# BCARDLIGHT.net
KiCad netlist of a schematic drawn in EAGLE
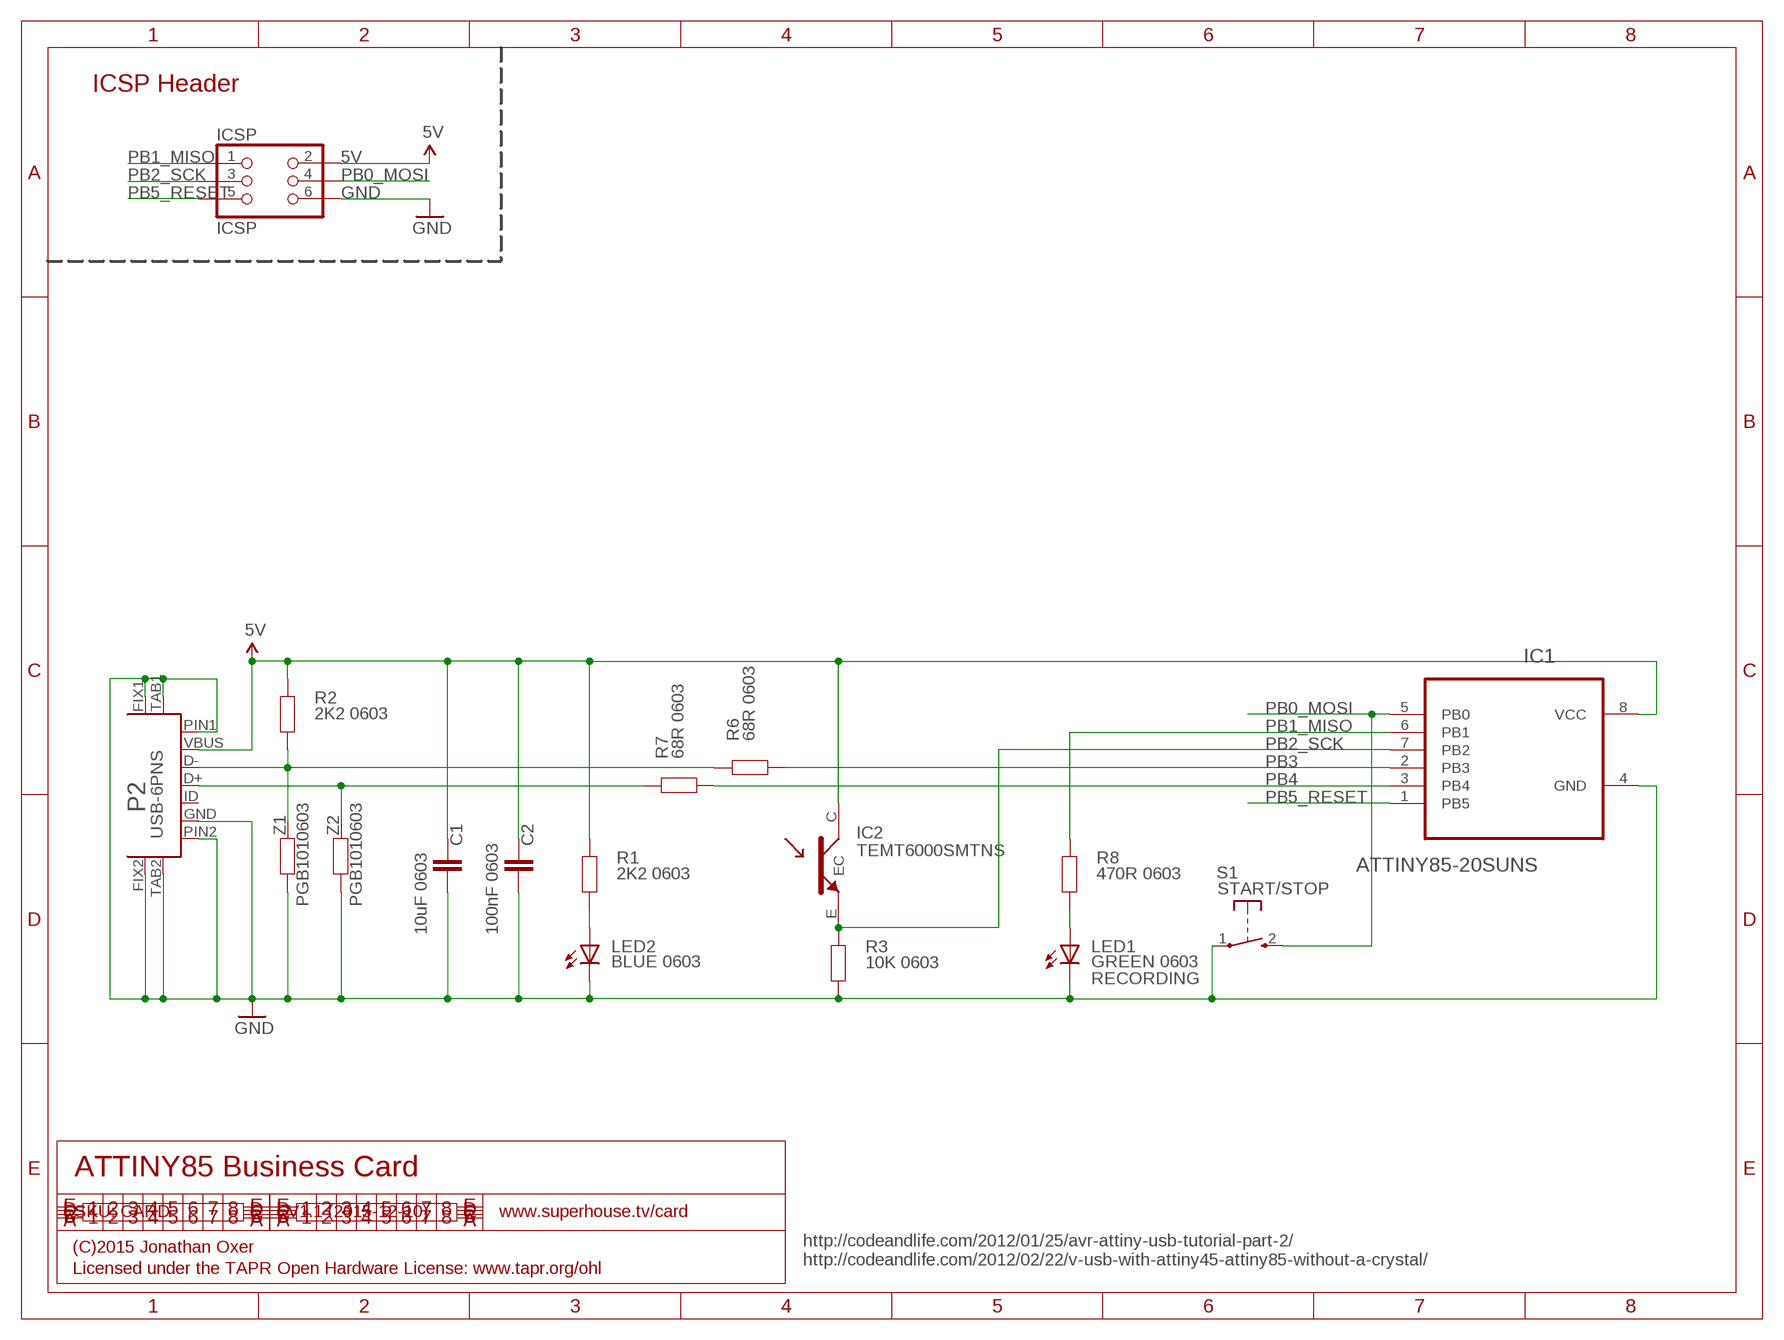
[diagram p0: schematic, sheet 1]

(export (version "E")
  (design (tool "Eeschema 10.0.6"))
  (components
    (comp (ref "C1")
      (value "10uF 0603")
      (footprint "eagle-import:0603_NO_SILK")
      (libsource (lib "eagle-import") (part "CAPNS"))
    )
    (comp (ref "C2")
      (value "100nF 0603")
      (footprint "eagle-import:0603_NO_SILK")
      (libsource (lib "eagle-import") (part "CAPNS"))
    )
    (comp (ref "IC1")
      (value "ATTINY85-20SUNS")
      (footprint "eagle-import:SOIC127P798X216-8N_NO_SILK")
      (libsource (lib "eagle-import") (part "ATTINY85-20SUNS"))
    )
    (comp (ref "IC2")
      (value "TEMT6000SMTNS")
      (footprint "eagle-import:TEMT6000_NO_SILK")
      (libsource (lib "eagle-import") (part "TEMT6000SMTNS"))
    )
    (comp (ref "ICSP")
      (value "ICSP")
      (footprint "eagle-import:2X03SURFACE_NO_SILK")
      (libsource (lib "eagle-import") (part "ICSPSMTNS"))
    )
    (comp (ref "LED1")
      (value "GREEN 0603")
      (footprint "eagle-import:0603_NO_SILK")
      (libsource (lib "eagle-import") (part "LED0603NS"))
    )
    (comp (ref "LED2")
      (value "BLUE 0603")
      (footprint "eagle-import:0603_NO_SILK")
      (libsource (lib "eagle-import") (part "LED0603NS"))
    )
    (comp (ref "P2")
      (value "USB-6PNS")
      (footprint "eagle-import:USB-MICROB-MB05PMXX_NO_SILK")
      (libsource (lib "eagle-import") (part "USB-6PNS"))
    )
    (comp (ref "R1")
      (value "2K2 0603")
      (footprint "eagle-import:0603_NO_SILK")
      (libsource (lib "eagle-import") (part "RESISTOR0603NS"))
    )
    (comp (ref "R2")
      (value "2K2 0603")
      (footprint "eagle-import:0603_NO_SILK")
      (libsource (lib "eagle-import") (part "RESISTOR0603NS"))
    )
    (comp (ref "R3")
      (value "10K 0603")
      (footprint "eagle-import:0603_NO_SILK")
      (libsource (lib "eagle-import") (part "RESISTOR0603NS"))
    )
    (comp (ref "R6")
      (value "68R 0603")
      (footprint "eagle-import:0603_NO_SILK")
      (libsource (lib "eagle-import") (part "RESISTOR0603NS"))
    )
    (comp (ref "R7")
      (value "68R 0603")
      (footprint "eagle-import:0603_NO_SILK")
      (libsource (lib "eagle-import") (part "RESISTOR0603NS"))
    )
    (comp (ref "R8")
      (value "470R 0603")
      (footprint "eagle-import:0603_NO_SILK")
      (libsource (lib "eagle-import") (part "RESISTOR0603NS"))
    )
    (comp (ref "S1")
      (value "START/STOP")
      (footprint "eagle-import:TACTILE_SWITCH_SMD_2PIN_TINY_NO_SILK")
      (libsource (lib "eagle-import") (part "TAC_SWITCH_2PINNS"))
    )
    (comp (ref "Z1")
      (value "PGB1010603")
      (footprint "eagle-import:0603_NO_SILK")
      (libsource (lib "eagle-import") (part "RESISTOR0603NS"))
    )
    (comp (ref "Z2")
      (value "PGB1010603")
      (footprint "eagle-import:0603_NO_SILK")
      (libsource (lib "eagle-import") (part "RESISTOR0603NS"))
    )
  )
  (nets
    (net (code "1") (name "/PB0_MOSI") (class "Default")
      (node (ref "IC1") (pin "5") (pinfunction "PB0_5") (pintype "bidirectional"))
      (node (ref "ICSP") (pin "4") (pinfunction "4_4") (pintype "passive"))
      (node (ref "S1") (pin "2") (pinfunction "S_2") (pintype "passive"))
    )
    (net (code "2") (name "/PB1_MISO") (class "Default")
      (node (ref "IC1") (pin "6") (pinfunction "PB1_6") (pintype "bidirectional"))
      (node (ref "ICSP") (pin "1") (pinfunction "1_1") (pintype "passive"))
      (node (ref "R8") (pin "2") (pinfunction "2_2") (pintype "passive"))
    )
    (net (code "3") (name "/PB2_SCK") (class "Default")
      (node (ref "IC1") (pin "7") (pinfunction "PB2_7") (pintype "bidirectional"))
      (node (ref "IC2") (pin "E") (pinfunction "E_E") (pintype "bidirectional"))
      (node (ref "ICSP") (pin "3") (pinfunction "3_3") (pintype "passive"))
      (node (ref "R3") (pin "2") (pinfunction "2_2") (pintype "passive"))
    )
    (net (code "4") (name "/PB3") (class "Default")
      (node (ref "IC1") (pin "2") (pinfunction "PB3_2") (pintype "bidirectional"))
      (node (ref "R6") (pin "1") (pinfunction "1_1") (pintype "passive"))
    )
    (net (code "5") (name "/PB4") (class "Default")
      (node (ref "IC1") (pin "3") (pinfunction "PB4_3") (pintype "bidirectional"))
      (node (ref "R7") (pin "1") (pinfunction "1_1") (pintype "passive"))
    )
    (net (code "6") (name "/PB5_RESET") (class "Default")
      (node (ref "IC1") (pin "1") (pinfunction "PB5_1") (pintype "bidirectional"))
      (node (ref "ICSP") (pin "5") (pinfunction "5_5") (pintype "passive"))
    )
    (net (code "7") (name "5V") (class "Default")
      (node (ref "C1") (pin "1") (pinfunction "1_1") (pintype "passive"))
      (node (ref "C2") (pin "1") (pinfunction "1_1") (pintype "passive"))
      (node (ref "IC1") (pin "8") (pinfunction "VCC_8") (pintype "power_in"))
      (node (ref "IC2") (pin "C") (pinfunction "C_C") (pintype "bidirectional"))
      (node (ref "ICSP") (pin "2") (pinfunction "2_2") (pintype "passive"))
      (node (ref "P2") (pin "VBUS") (pinfunction "VBUS_VBUS") (pintype "bidirectional"))
      (node (ref "R1") (pin "2") (pinfunction "2_2") (pintype "passive"))
      (node (ref "R2") (pin "2") (pinfunction "2_2") (pintype "passive"))
    )
    (net (code "8") (name "GND") (class "Default")
      (node (ref "C1") (pin "2") (pinfunction "2_2") (pintype "passive"))
      (node (ref "C2") (pin "2") (pinfunction "2_2") (pintype "passive"))
      (node (ref "IC1") (pin "4") (pinfunction "GND_4") (pintype "passive"))
      (node (ref "ICSP") (pin "6") (pinfunction "6_6") (pintype "passive"))
      (node (ref "LED1") (pin "2") (pinfunction "C_2") (pintype "passive"))
      (node (ref "LED2") (pin "2") (pinfunction "C_2") (pintype "passive"))
      (node (ref "P2") (pin "FIX1") (pinfunction "FIX1_FIX1") (pintype "bidirectional"))
      (node (ref "P2") (pin "FIX2") (pinfunction "FIX2_FIX2") (pintype "bidirectional"))
      (node (ref "P2") (pin "GND") (pinfunction "GND_GND") (pintype "bidirectional"))
      (node (ref "P2") (pin "PIN1") (pinfunction "PIN1_PIN1") (pintype "bidirectional"))
      (node (ref "P2") (pin "PIN2") (pinfunction "PIN2_PIN2") (pintype "bidirectional"))
      (node (ref "P2") (pin "TAB1") (pinfunction "TAB1_TAB1") (pintype "bidirectional"))
      (node (ref "P2") (pin "TAB2") (pinfunction "TAB2_TAB2") (pintype "bidirectional"))
      (node (ref "R3") (pin "1") (pinfunction "1_1") (pintype "passive"))
      (node (ref "S1") (pin "1") (pinfunction "P_1") (pintype "passive"))
      (node (ref "Z1") (pin "1") (pinfunction "1_1") (pintype "passive"))
      (node (ref "Z2") (pin "1") (pinfunction "1_1") (pintype "passive"))
    )
    (net (code "9") (name "Net-(LED1-A)") (class "Default")
      (node (ref "LED1") (pin "1") (pinfunction "A_1") (pintype "passive"))
      (node (ref "R8") (pin "1") (pinfunction "1_1") (pintype "passive"))
    )
    (net (code "10") (name "Net-(LED2-A)") (class "Default")
      (node (ref "LED2") (pin "1") (pinfunction "A_1") (pintype "passive"))
      (node (ref "R1") (pin "1") (pinfunction "1_1") (pintype "passive"))
    )
    (net (code "11") (name "Net-(P2-PadD+)") (class "Default")
      (node (ref "P2") (pin "D+") (pinfunction "D+_D+") (pintype "bidirectional"))
      (node (ref "R7") (pin "2") (pinfunction "2_2") (pintype "passive"))
      (node (ref "Z2") (pin "2") (pinfunction "2_2") (pintype "passive"))
    )
    (net (code "12") (name "Net-(P2-PadD-)") (class "Default")
      (node (ref "P2") (pin "D-") (pinfunction "D-_D-") (pintype "bidirectional"))
      (node (ref "R2") (pin "1") (pinfunction "1_1") (pintype "passive"))
      (node (ref "R6") (pin "2") (pinfunction "2_2") (pintype "passive"))
      (node (ref "Z1") (pin "2") (pinfunction "2_2") (pintype "passive"))
    )
    (net (code "13") (name "unconnected-(P2-PadID)") (class "Default")
      (node (ref "P2") (pin "ID") (pinfunction "ID_ID") (pintype "bidirectional"))
    )
  )
)
